# Sheet-Battery-V1_0.net
KiCad netlist of a schematic drawn in Altium Designer
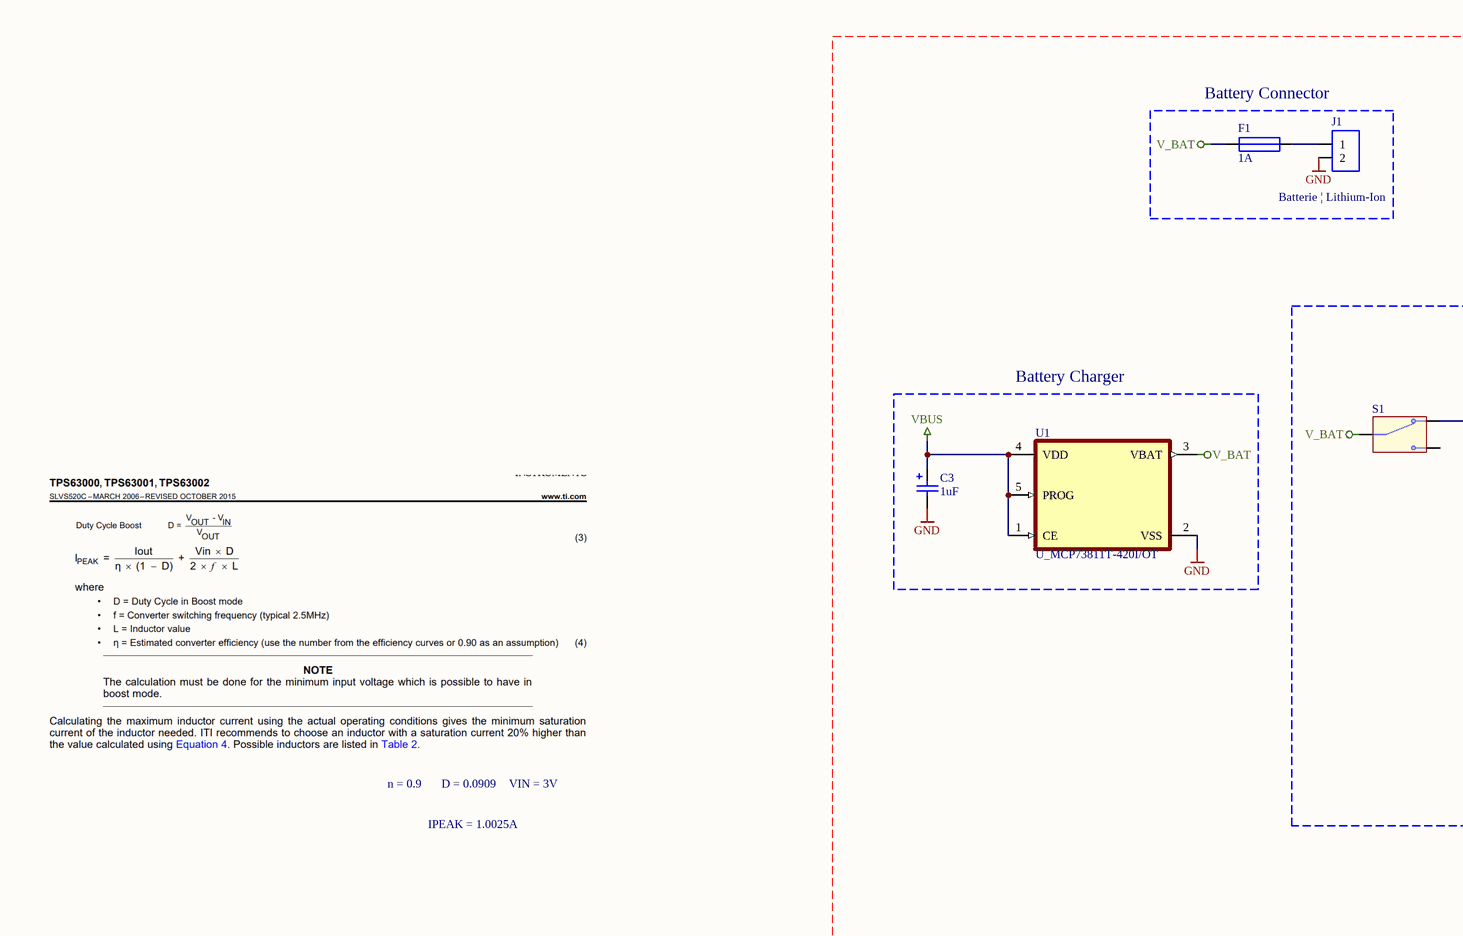
[diagram p0: Sheet-Battery-V1.0.SchDoc, left]
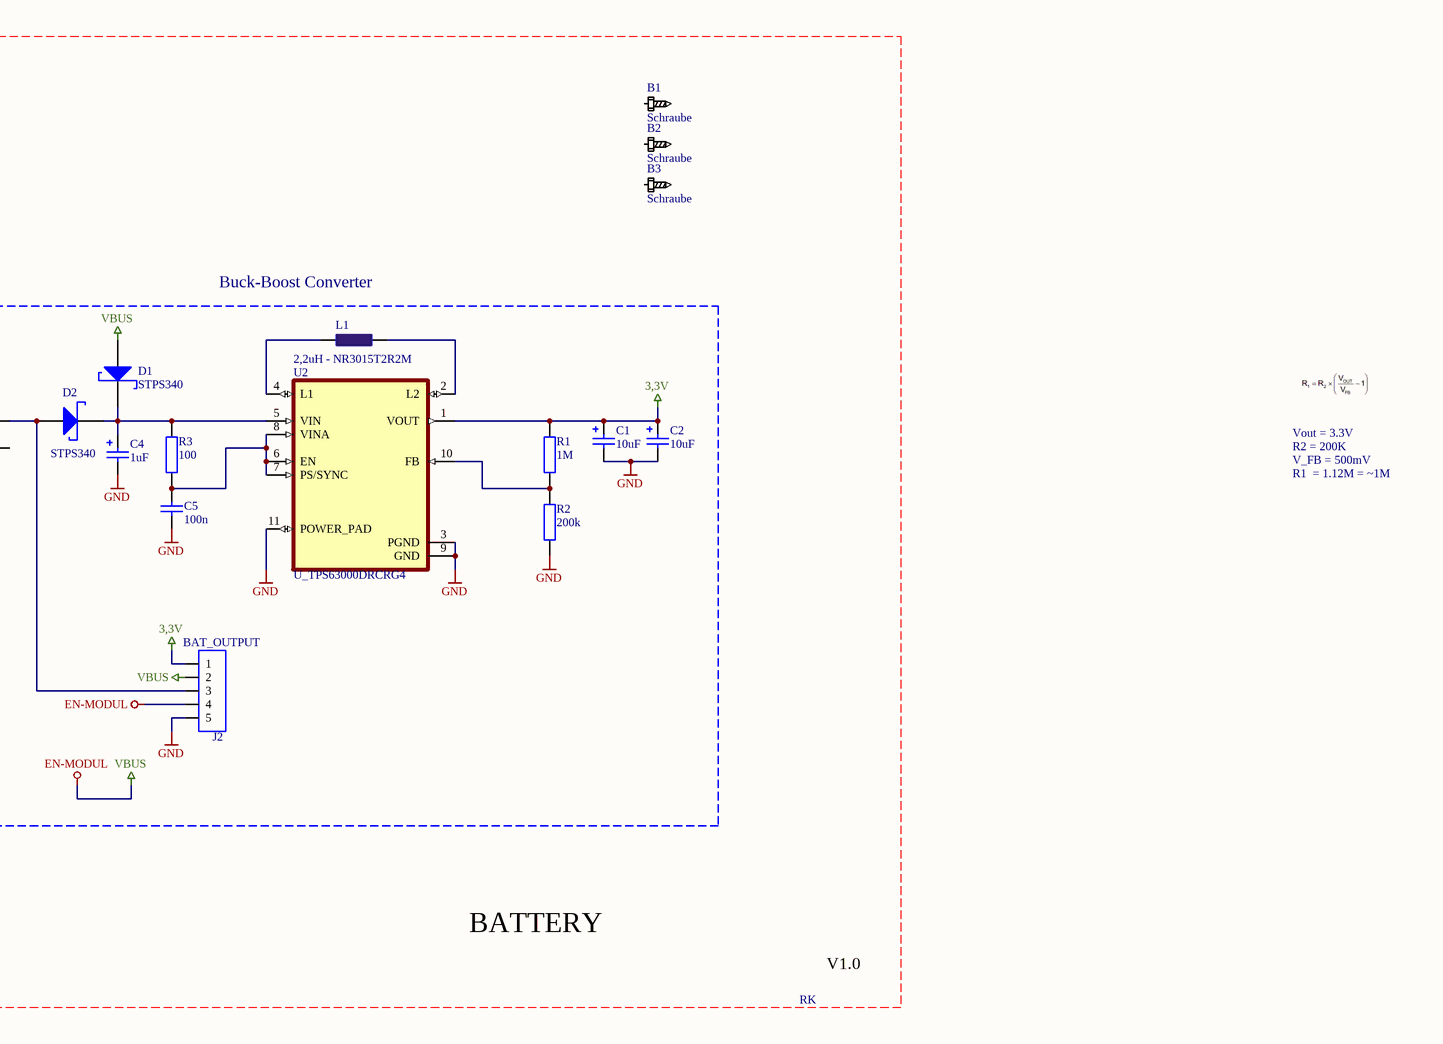
[diagram p1: Sheet-Battery-V1.0.SchDoc, right]

(export (version "E")
  (design (tool "Eeschema 10.0.6"))
  (components
    (comp (ref "B1")
      (value "Schraube")
      (footprint "B_Schraube-M3 PAD")
      (description "Schraubenloch für M3 Schrauben")
      (libsource (lib "SCHLIB-PCSB_5.1.3") (part "B_Schraube"))
    )
    (comp (ref "B2")
      (value "Schraube")
      (footprint "B_Schraube-M3 PAD")
      (description "Schraubenloch für M3 Schrauben")
      (libsource (lib "SCHLIB-PCSB_5.1.3") (part "B_Schraube"))
    )
    (comp (ref "B3")
      (value "Schraube")
      (footprint "B_Schraube-M3 PAD")
      (description "Schraubenloch für M3 Schrauben")
      (libsource (lib "SCHLIB-PCSB_5.1.3") (part "B_Schraube"))
    )
    (comp (ref "C1")
      (value "10uF")
      (footprint "C_SMD_B-Typ")
      (description "SMD Elektrolytkondensator")
      (libsource (lib "SCHLIB-PCSB_5.1.3") (part "C_SMD_ELK"))
    )
    (comp (ref "C2")
      (value "10uF")
      (footprint "C_SMD_B-Typ")
      (description "SMD Elektrolytkondensator")
      (libsource (lib "SCHLIB-PCSB_5.1.3") (part "C_SMD_ELK"))
    )
    (comp (ref "C3")
      (value "1uF")
      (footprint "C_SMD_B-Typ")
      (description "SMD Elektrolytkondensator")
      (libsource (lib "SCHLIB-PCSB_5.1.3") (part "C_SMD_ELK"))
    )
    (comp (ref "C4")
      (value "1uF")
      (footprint "C_SMD_B-Typ")
      (description "SMD Elektrolytkondensator")
      (libsource (lib "SCHLIB-PCSB_5.1.3") (part "C_SMD_ELK"))
    )
    (comp (ref "C5")
      (value "100n")
      (footprint "C_SMD_0603")
      (description "Kondensator SMD Universal, Keramik, Folie, usw.")
      (libsource (lib "SCHLIB-PCSB_5.1.3") (part "C_SMD_KO"))
    )
    (comp (ref "D1")
      (value "STPS340")
      (footprint "D_DO-214")
      (description "Diode SMD Schottky")
      (libsource (lib "SCHLIB-PCSB_5.1.3") (part "D_SMD_Schottky"))
    )
    (comp (ref "D2")
      (value "STPS340")
      (footprint "D_DO-214")
      (description "Diode SMD Schottky")
      (libsource (lib "SCHLIB-PCSB_5.1.3") (part "D_SMD_Schottky"))
    )
    (comp (ref "F1")
      (value "1A")
      (footprint "F_OMF63_Schurtner")
      (description "Sicherung")
      (libsource (lib "SCHLIB-PCSB_5.1.3") (part "F_THT_Fuse"))
    )
    (comp (ref "J1")
      (value "Batterie ¦ Lithium-Ion")
      (footprint "J_THT_Printklemme 2x")
      (description "Stecker")
      (libsource (lib "SCHLIB-PCSB_5.1.3") (part "J_THT_CON2"))
    )
    (comp (ref "J2")
      (value "BAT_OUTPUT")
      (footprint "SIP-5")
      (description "Stecker")
      (libsource (lib "SCHLIB-PCSB_5.1.3") (part "J_THT_CON5"))
    )
    (comp (ref "L1")
      (value "2,2uH - NR3015T2R2M")
      (footprint "L_SMD_ND_NR3015T2R2M")
      (description "Spule SMD")
      (libsource (lib "SCHLIB-PCSB_5.1.3") (part "L_SMD_Spule"))
    )
    (comp (ref "R1")
      (value "1M")
      (footprint "R_SMD_0805")
      (description "Widerstand SMD")
      (libsource (lib "SCHLIB-PCSB_5.1.3") (part "R_SMD_Widerstand"))
    )
    (comp (ref "R2")
      (value "200k")
      (footprint "R_SMD_0805")
      (description "Widerstand SMD")
      (libsource (lib "SCHLIB-PCSB_5.1.3") (part "R_SMD_Widerstand"))
    )
    (comp (ref "R3")
      (value "100")
      (footprint "R_SMD_0805")
      (description "Widerstand SMD")
      (libsource (lib "SCHLIB-PCSB_5.1.3") (part "R_SMD_Widerstand"))
    )
    (comp (ref "S1")
      (value "~")
      (footprint "S_THT_SW-3Pol")
      (description "Toggle Switch")
      (fields (field (name "MP") "100SP1T1B4M2QE"))
      (libsource (lib "SCHLIB-PCSB_5.1.3") (part "S_THT_Schalter 3-Pol."))
    )
    (comp (ref "U1")
      (value "U_MCP73811T-420I/OT")
      (footprint "SOT95P280X145-5N")
      (description "Charger IC Lithium Ion/Polymer SOT-23-5")
      (fields (field (name "MF") "Microchip") (field (name "MP") "MCP73811T-420I/OT"))
      (libsource (lib "SCHLIB-PCSB_5.1.3") (part "U_MCP73811T-420I/OT"))
    )
    (comp (ref "U2")
      (value "U_TPS63000DRCRG4")
      (footprint "VREG_V62/16624-01YE")
      (description "High efficiency Buck-Boost Converter with 1.8A Current Switches in 3x3 QFN 10-VSON -40 to 85")
      (fields (field (name "MF") "Texas Instruments") (field (name "MP") "TPS63000DRCRG4"))
      (libsource (lib "SCHLIB-PCSB_5.1.3") (part "U_TPS63000DRCRG4"))
    )
  )
  (nets
    (net (code "1") (name "3,3V") (class "Default")
      (node (ref "C1") (pin "1") (pinfunction "1_1") (pintype "passive"))
      (node (ref "C2") (pin "1") (pinfunction "1_1") (pintype "passive"))
      (node (ref "J2") (pin "1") (pinfunction "1_1") (pintype "passive"))
      (node (ref "R1") (pin "2") (pintype "passive"))
      (node (ref "U2") (pin "1") (pinfunction "VOUT_1") (pintype "output"))
    )
    (net (code "2") (name "EN-MODUL") (class "Default")
      (node (ref "C3") (pin "1") (pinfunction "1_1") (pintype "passive"))
      (node (ref "D1") (pin "1") (pinfunction "A_1") (pintype "passive"))
      (node (ref "J2") (pin "2") (pinfunction "2_2") (pintype "passive"))
      (node (ref "J2") (pin "4") (pinfunction "4_4") (pintype "passive"))
      (node (ref "U1") (pin "1") (pinfunction "CE_1") (pintype "input"))
      (node (ref "U1") (pin "4") (pinfunction "VDD_4") (pintype "power_in"))
      (node (ref "U1") (pin "5") (pinfunction "PROG_5") (pintype "input"))
    )
    (net (code "3") (name "GND") (class "Default")
      (node (ref "C1") (pin "2") (pinfunction "2_2") (pintype "passive"))
      (node (ref "C2") (pin "2") (pinfunction "2_2") (pintype "passive"))
      (node (ref "C3") (pin "2") (pinfunction "2_2") (pintype "passive"))
      (node (ref "C4") (pin "2") (pinfunction "2_2") (pintype "passive"))
      (node (ref "C5") (pin "2") (pintype "passive"))
      (node (ref "J1") (pin "2") (pinfunction "2_2") (pintype "passive"))
      (node (ref "J2") (pin "5") (pinfunction "5_5") (pintype "passive"))
      (node (ref "R2") (pin "1") (pintype "passive"))
      (node (ref "U1") (pin "2") (pinfunction "VSS_2") (pintype "power_in"))
      (node (ref "U2") (pin "11") (pinfunction "POWER_PAD_11") (pintype "bidirectional"))
      (node (ref "U2") (pin "3") (pinfunction "PGND_3") (pintype "power_in"))
      (node (ref "U2") (pin "9") (pinfunction "GND_9") (pintype "power_in"))
    )
    (net (code "4") (name "Net-(D1-K)") (class "Default")
      (node (ref "C4") (pin "1") (pinfunction "1_1") (pintype "passive"))
      (node (ref "D1") (pin "2") (pinfunction "K_2") (pintype "passive"))
      (node (ref "D2") (pin "2") (pinfunction "K_2") (pintype "passive"))
      (node (ref "R3") (pin "2") (pintype "passive"))
      (node (ref "U2") (pin "5") (pinfunction "VIN_5") (pintype "input"))
    )
    (net (code "5") (name "Net-(D2-A)") (class "Default")
      (node (ref "D2") (pin "1") (pinfunction "A_1") (pintype "passive"))
      (node (ref "J2") (pin "3") (pinfunction "3_3") (pintype "passive"))
      (node (ref "S1") (pin "1") (pinfunction "1_1") (pintype "passive"))
    )
    (net (code "6") (name "Net-(F1-Pad2)") (class "Default")
      (node (ref "F1") (pin "2") (pinfunction "2_2") (pintype "passive"))
      (node (ref "J1") (pin "1") (pinfunction "1_1") (pintype "passive"))
    )
    (net (code "7") (name "Net-(U2-EN)") (class "Default")
      (node (ref "C5") (pin "1") (pintype "passive"))
      (node (ref "R3") (pin "1") (pintype "passive"))
      (node (ref "U2") (pin "6") (pinfunction "EN_6") (pintype "input"))
      (node (ref "U2") (pin "7") (pinfunction "PS/SYNC_7") (pintype "input"))
      (node (ref "U2") (pin "8") (pinfunction "VINA_8") (pintype "input"))
    )
    (net (code "8") (name "Net-(U2-FB)") (class "Default")
      (node (ref "R1") (pin "1") (pintype "passive"))
      (node (ref "R2") (pin "2") (pintype "passive"))
      (node (ref "U2") (pin "10") (pinfunction "FB_10") (pintype "input"))
    )
    (net (code "9") (name "Net-(U2-L1)") (class "Default")
      (node (ref "L1") (pin "2") (pintype "passive"))
      (node (ref "U2") (pin "4") (pinfunction "L1_4") (pintype "bidirectional"))
    )
    (net (code "10") (name "Net-(U2-L2)") (class "Default")
      (node (ref "L1") (pin "1") (pintype "passive"))
      (node (ref "U2") (pin "2") (pinfunction "L2_2") (pintype "bidirectional"))
    )
    (net (code "11") (name "V_BAT") (class "Default")
      (node (ref "F1") (pin "1") (pintype "passive"))
      (node (ref "S1") (pin "2") (pinfunction "2_2") (pintype "passive"))
      (node (ref "U1") (pin "3") (pinfunction "VBAT_3") (pintype "output"))
    )
    (net (code "12") (name "unconnected-(B1-PAD-Pad1)") (class "Default")
      (node (ref "B1") (pin "1") (pinfunction "PAD_1") (pintype "passive"))
    )
    (net (code "13") (name "unconnected-(B2-PAD-Pad1)") (class "Default")
      (node (ref "B2") (pin "1") (pinfunction "PAD_1") (pintype "passive"))
    )
    (net (code "14") (name "unconnected-(B3-PAD-Pad1)") (class "Default")
      (node (ref "B3") (pin "1") (pinfunction "PAD_1") (pintype "passive"))
    )
    (net (code "15") (name "unconnected-(S1-Pad3)") (class "Default")
      (node (ref "S1") (pin "3") (pinfunction "3_3") (pintype "passive"))
    )
  )
)
